# DigitalPSU.net
KiCad netlist of a schematic drawn in EAGLE
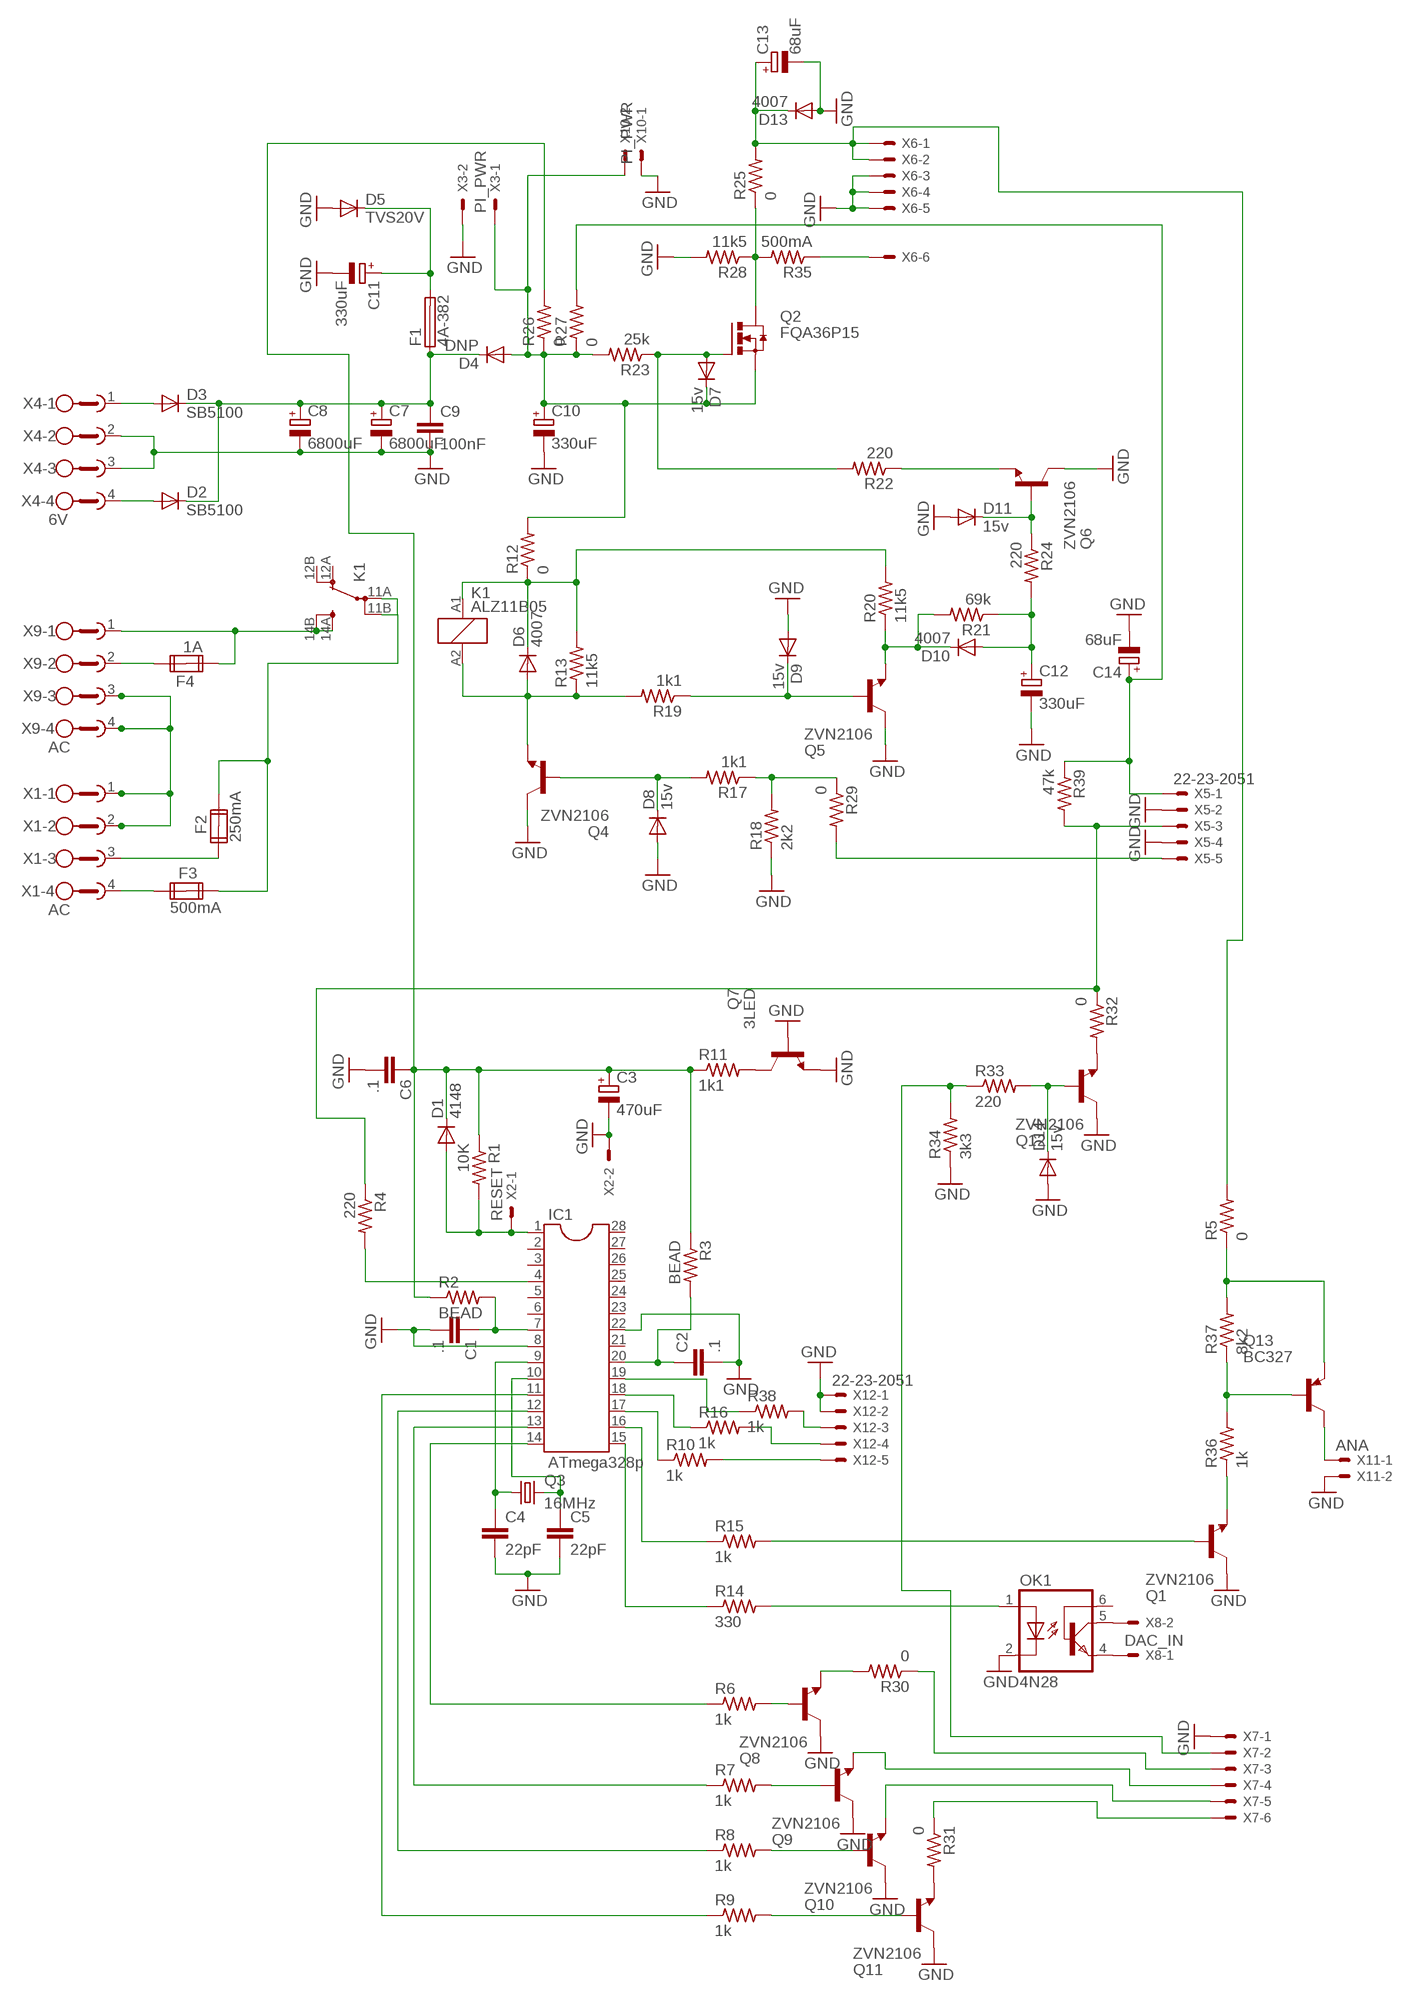
[diagram p0: schematic, sheet 1]

(export (version "E")
  (design (tool "Eeschema 10.0.6"))
  (components
    (comp (ref "C1")
      (value ".1")
      (footprint "eagle-import:C1210K")
      (libsource (lib "eagle-import") (part "C-EUC1210K"))
    )
    (comp (ref "C2")
      (value ".1")
      (footprint "eagle-import:C1210K")
      (libsource (lib "eagle-import") (part "C-EUC1210K"))
    )
    (comp (ref "C3")
      (value "470uF")
      (footprint "eagle-import:E3,5-10")
      (libsource (lib "eagle-import") (part "CPOL-EUE3.5-10"))
    )
    (comp (ref "C4")
      (value "22pF")
      (footprint "eagle-import:C1210K")
      (libsource (lib "eagle-import") (part "C-EUC1210K"))
    )
    (comp (ref "C5")
      (value "22pF")
      (footprint "eagle-import:C1210K")
      (libsource (lib "eagle-import") (part "C-EUC1210K"))
    )
    (comp (ref "C6")
      (value ".1")
      (footprint "eagle-import:C1210K")
      (libsource (lib "eagle-import") (part "C-EUC1210K"))
    )
    (comp (ref "C7")
      (value "6800uF")
      (footprint "eagle-import:EB20D")
      (libsource (lib "eagle-import") (part "CPOL-EUE10-20"))
    )
    (comp (ref "C8")
      (value "6800uF")
      (footprint "eagle-import:EB20D")
      (libsource (lib "eagle-import") (part "CPOL-EUE10-20"))
    )
    (comp (ref "C9")
      (value "100nF")
      (footprint "eagle-import:C10B6")
      (libsource (lib "eagle-import") (part "C10/6"))
    )
    (comp (ref "C10")
      (value "330uF")
      (footprint "eagle-import:E3,5-10")
      (libsource (lib "eagle-import") (part "CPOL-EUE3.5-10"))
    )
    (comp (ref "C11")
      (value "330uF")
      (footprint "eagle-import:E3,5-10")
      (libsource (lib "eagle-import") (part "CPOL-EUE3.5-10"))
    )
    (comp (ref "C12")
      (value "330uF")
      (footprint "eagle-import:E3,5-10")
      (libsource (lib "eagle-import") (part "CPOL-EUE3.5-10"))
    )
    (comp (ref "C13")
      (value "68uF")
      (footprint "eagle-import:E3,5-10")
      (libsource (lib "eagle-import") (part "CPOL-EUE3.5-10"))
    )
    (comp (ref "C14")
      (value "68uF")
      (footprint "eagle-import:E3,5-10")
      (libsource (lib "eagle-import") (part "CPOL-EUE3.5-10"))
    )
    (comp (ref "D1")
      (value "4148")
      (footprint "eagle-import:DO35-7")
      (libsource (lib "eagle-import") (part "1N4148DO35-7"))
    )
    (comp (ref "D2")
      (value "SB5100")
      (footprint "eagle-import:SOD57-10")
      (libsource (lib "eagle-import") (part "BY448"))
    )
    (comp (ref "D3")
      (value "SB5100")
      (footprint "eagle-import:SOD57-10")
      (libsource (lib "eagle-import") (part "BY448"))
    )
    (comp (ref "D4")
      (value "DNP")
      (footprint "eagle-import:DO41-10")
      (libsource (lib "eagle-import") (part "1N4004"))
    )
    (comp (ref "D5")
      (value "TVS20V")
      (footprint "eagle-import:SOD57-10")
      (libsource (lib "eagle-import") (part "BY448"))
    )
    (comp (ref "D6")
      (value "4007")
      (footprint "eagle-import:DO41-10")
      (libsource (lib "eagle-import") (part "1N4004"))
    )
    (comp (ref "D7")
      (value "15v")
      (footprint "eagle-import:DO35-10")
      (libsource (lib "eagle-import") (part "1N4148DO35-10"))
    )
    (comp (ref "D8")
      (value "15v")
      (footprint "eagle-import:DO35-7")
      (libsource (lib "eagle-import") (part "1N4148DO35-7"))
    )
    (comp (ref "D9")
      (value "15v")
      (footprint "eagle-import:DO35-7")
      (libsource (lib "eagle-import") (part "1N4148DO35-7"))
    )
    (comp (ref "D10")
      (value "4007")
      (footprint "eagle-import:DO35-10")
      (libsource (lib "eagle-import") (part "1N4148DO35-10"))
    )
    (comp (ref "D11")
      (value "15v")
      (footprint "eagle-import:DO35-7")
      (libsource (lib "eagle-import") (part "1N4148DO35-7"))
    )
    (comp (ref "D13")
      (value "4007")
      (footprint "eagle-import:DO41-10")
      (libsource (lib "eagle-import") (part "1N4004"))
    )
    (comp (ref "D14")
      (value "15v")
      (footprint "eagle-import:DO35-7")
      (libsource (lib "eagle-import") (part "1N4148DO35-7"))
    )
    (comp (ref "F1")
      (value "4A-382")
      (footprint "eagle-import:19560")
      (fields (field (name "MPN") "56000001009"))
      (libsource (lib "eagle-import") (part "19560"))
    )
    (comp (ref "F2")
      (value "250mA")
      (footprint "eagle-import:FUSE1")
      (libsource (lib "eagle-import") (part "FUSE2P"))
    )
    (comp (ref "F3")
      (value "500mA")
      (footprint "eagle-import:FUSE1")
      (libsource (lib "eagle-import") (part "FUSE2P"))
    )
    (comp (ref "F4")
      (value "1A")
      (footprint "eagle-import:FUSE1")
      (libsource (lib "eagle-import") (part "FUSE2P"))
    )
    (comp (ref "IC1")
      (value "ATmega328p")
      (footprint "eagle-import:DIL28-3")
      (libsource (lib "eagle-import") (part "DIL28-3"))
    )
    (comp (ref "K1")
      (value "ALZ11B05")
      (footprint "eagle-import:RT-C_O16A5")
      (fields (field (name "MPN") "RT314730"))
      (libsource (lib "eagle-import") (part "RT314730"))
    )
    (comp (ref "OK1")
      (value "4N28")
      (footprint "eagle-import:DIL06")
      (fields (field (name "MF") "FAIRCHILD SEMICONDUCTOR") (field (name "MPN") "4N35"))
      (libsource (lib "eagle-import") (part "4N35"))
    )
    (comp (ref "Q1")
      (value "ZVN2106")
      (footprint "eagle-import:TO92-EBC")
      (libsource (lib "eagle-import") (part "BC550B"))
    )
    (comp (ref "Q2")
      (value "FQA36P15")
      (footprint "eagle-import:TO247BV")
      (libsource (lib "eagle-import") (part "IRFP240"))
    )
    (comp (ref "Q3")
      (value "16MHz")
      (footprint "eagle-import:HC49_S")
      (libsource (lib "eagle-import") (part "CRYSTALHC49S"))
    )
    (comp (ref "Q4")
      (value "ZVN2106")
      (footprint "eagle-import:TO92-EBC")
      (libsource (lib "eagle-import") (part "BC550B"))
    )
    (comp (ref "Q5")
      (value "ZVN2106")
      (footprint "eagle-import:TO92-EBC")
      (libsource (lib "eagle-import") (part "BC550B"))
    )
    (comp (ref "Q6")
      (value "ZVN2106")
      (footprint "eagle-import:TO92-EBC")
      (libsource (lib "eagle-import") (part "BC550B"))
    )
    (comp (ref "Q7")
      (value "3LED")
      (footprint "eagle-import:TO92-EBC")
      (libsource (lib "eagle-import") (part "BC546A"))
    )
    (comp (ref "Q8")
      (value "ZVN2106")
      (footprint "eagle-import:TO92-EBC")
      (libsource (lib "eagle-import") (part "BC550B"))
    )
    (comp (ref "Q9")
      (value "ZVN2106")
      (footprint "eagle-import:TO92-EBC")
      (libsource (lib "eagle-import") (part "BC550B"))
    )
    (comp (ref "Q10")
      (value "ZVN2106")
      (footprint "eagle-import:TO92-EBC")
      (libsource (lib "eagle-import") (part "BC550B"))
    )
    (comp (ref "Q11")
      (value "ZVN2106")
      (footprint "eagle-import:TO92-EBC")
      (libsource (lib "eagle-import") (part "BC550B"))
    )
    (comp (ref "Q12")
      (value "ZVN2106")
      (footprint "eagle-import:TO92-EBC")
      (libsource (lib "eagle-import") (part "BC550B"))
    )
    (comp (ref "Q13")
      (value "BC327")
      (footprint "eagle-import:TO92-EBC")
      (libsource (lib "eagle-import") (part "BC327-25"))
    )
    (comp (ref "R1")
      (value "10K")
      (footprint "eagle-import:0309_10")
      (libsource (lib "eagle-import") (part "R-US_0309/10"))
    )
    (comp (ref "R2")
      (value "BEAD")
      (footprint "eagle-import:0309_10")
      (libsource (lib "eagle-import") (part "R-US_0309/10"))
    )
    (comp (ref "R3")
      (value "BEAD")
      (footprint "eagle-import:0309_12")
      (libsource (lib "eagle-import") (part "R-US_0309/12"))
    )
    (comp (ref "R4")
      (value "220")
      (footprint "eagle-import:0309_12")
      (libsource (lib "eagle-import") (part "R-US_0309/12"))
    )
    (comp (ref "R5")
      (value "0")
      (footprint "eagle-import:0309_12")
      (libsource (lib "eagle-import") (part "R-US_0309/12"))
    )
    (comp (ref "R6")
      (value "1k")
      (footprint "eagle-import:R1210")
      (libsource (lib "eagle-import") (part "R-US_R1210"))
    )
    (comp (ref "R7")
      (value "1k")
      (footprint "eagle-import:R1210")
      (libsource (lib "eagle-import") (part "R-US_R1210"))
    )
    (comp (ref "R8")
      (value "1k")
      (footprint "eagle-import:R1210")
      (libsource (lib "eagle-import") (part "R-US_R1210"))
    )
    (comp (ref "R9")
      (value "1k")
      (footprint "eagle-import:R1210")
      (libsource (lib "eagle-import") (part "R-US_R1210"))
    )
    (comp (ref "R10")
      (value "1k")
      (footprint "eagle-import:R1210")
      (libsource (lib "eagle-import") (part "R-US_R1210"))
    )
    (comp (ref "R11")
      (value "1k1")
      (footprint "eagle-import:0309_10")
      (libsource (lib "eagle-import") (part "R-US_0309/10"))
    )
    (comp (ref "R12")
      (value "0")
      (footprint "eagle-import:0309_10")
      (libsource (lib "eagle-import") (part "R-US_0309/10"))
    )
    (comp (ref "R13")
      (value "11k5")
      (footprint "eagle-import:0309_10")
      (libsource (lib "eagle-import") (part "R-US_0309/10"))
    )
    (comp (ref "R14")
      (value "330")
      (footprint "eagle-import:0309_10")
      (libsource (lib "eagle-import") (part "R-US_0309/10"))
    )
    (comp (ref "R15")
      (value "1k")
      (footprint "eagle-import:R1210")
      (libsource (lib "eagle-import") (part "R-US_R1210"))
    )
    (comp (ref "R16")
      (value "1k")
      (footprint "eagle-import:R1210")
      (libsource (lib "eagle-import") (part "R-US_R1210"))
    )
    (comp (ref "R17")
      (value "1k1")
      (footprint "eagle-import:0309_10")
      (libsource (lib "eagle-import") (part "R-US_0309/10"))
    )
    (comp (ref "R18")
      (value "2k2")
      (footprint "eagle-import:0309_10")
      (libsource (lib "eagle-import") (part "R-US_0309/10"))
    )
    (comp (ref "R19")
      (value "1k1")
      (footprint "eagle-import:0309_10")
      (libsource (lib "eagle-import") (part "R-US_0309/10"))
    )
    (comp (ref "R20")
      (value "11k5")
      (footprint "eagle-import:0309_10")
      (libsource (lib "eagle-import") (part "R-US_0309/10"))
    )
    (comp (ref "R21")
      (value "69k")
      (footprint "eagle-import:0309_10")
      (libsource (lib "eagle-import") (part "R-US_0309/10"))
    )
    (comp (ref "R22")
      (value "220")
      (footprint "eagle-import:0309_10")
      (libsource (lib "eagle-import") (part "R-US_0309/10"))
    )
    (comp (ref "R23")
      (value "25k")
      (footprint "eagle-import:0309_10")
      (libsource (lib "eagle-import") (part "R-US_0309/10"))
    )
    (comp (ref "R24")
      (value "220")
      (footprint "eagle-import:0309_10")
      (libsource (lib "eagle-import") (part "R-US_0309/10"))
    )
    (comp (ref "R25")
      (value "0")
      (footprint "eagle-import:0309_12")
      (libsource (lib "eagle-import") (part "R-US_0309/12"))
    )
    (comp (ref "R26")
      (value "0")
      (footprint "eagle-import:0309_12")
      (libsource (lib "eagle-import") (part "R-US_0309/12"))
    )
    (comp (ref "R27")
      (value "0")
      (footprint "eagle-import:0309_12")
      (libsource (lib "eagle-import") (part "R-US_0309/12"))
    )
    (comp (ref "R28")
      (value "11k5")
      (footprint "eagle-import:0204_5")
      (libsource (lib "eagle-import") (part "R-US_0204/5"))
    )
    (comp (ref "R29")
      (value "0")
      (footprint "eagle-import:0309_10")
      (libsource (lib "eagle-import") (part "R-US_0309/10"))
    )
    (comp (ref "R30")
      (value "0")
      (footprint "eagle-import:0309_10")
      (libsource (lib "eagle-import") (part "R-US_0309/10"))
    )
    (comp (ref "R31")
      (value "0")
      (footprint "eagle-import:0309_12")
      (libsource (lib "eagle-import") (part "R-US_0309/12"))
    )
    (comp (ref "R32")
      (value "0")
      (footprint "eagle-import:0309_12")
      (libsource (lib "eagle-import") (part "R-US_0309/12"))
    )
    (comp (ref "R33")
      (value "220")
      (footprint "eagle-import:0309_12")
      (libsource (lib "eagle-import") (part "R-US_0309/12"))
    )
    (comp (ref "R34")
      (value "3k3")
      (footprint "eagle-import:0309_12")
      (libsource (lib "eagle-import") (part "R-US_0309/12"))
    )
    (comp (ref "R35")
      (value "500mA")
      (footprint "eagle-import:0204_5")
      (libsource (lib "eagle-import") (part "R-US_0204/5"))
    )
    (comp (ref "R36")
      (value "1k")
      (footprint "eagle-import:R1210")
      (libsource (lib "eagle-import") (part "R-US_R1210"))
    )
    (comp (ref "R37")
      (value "8k2")
      (footprint "eagle-import:R1210")
      (libsource (lib "eagle-import") (part "R-US_R1210"))
    )
    (comp (ref "R38")
      (value "1k")
      (footprint "eagle-import:R1210")
      (libsource (lib "eagle-import") (part "R-US_R1210"))
    )
    (comp (ref "R39")
      (value "47k")
      (footprint "eagle-import:0309_10")
      (libsource (lib "eagle-import") (part "R-US_0309/10"))
    )
    (comp (ref "X1")
      (value "AC")
      (footprint "eagle-import:GMSTBA4")
      (fields (field (name "MF") "FARNELL") (field (name "MPN") "1757268"))
      (libsource (lib "eagle-import") (part "GMSTBA4"))
    )
    (comp (ref "X2")
      (value "RESET")
      (footprint "eagle-import:22-23-2021")
      (fields (field (name "MF") "MOLEX") (field (name "MPN") "22-23-2021"))
      (libsource (lib "eagle-import") (part "22-23-2021"))
    )
    (comp (ref "X3")
      (value "PI_PWR")
      (footprint "eagle-import:22-23-2021")
      (fields (field (name "MF") "MOLEX") (field (name "MPN") "22-23-2021"))
      (libsource (lib "eagle-import") (part "22-23-2021"))
    )
    (comp (ref "X4")
      (value "6V")
      (footprint "eagle-import:GMSTBA4")
      (fields (field (name "MF") "FARNELL") (field (name "MPN") "1757268"))
      (libsource (lib "eagle-import") (part "GMSTBA4"))
    )
    (comp (ref "X5")
      (value "22-23-2051")
      (footprint "eagle-import:22-23-2051")
      (fields (field (name "MF") "MOLEX"))
      (libsource (lib "eagle-import") (part "22-23-2051"))
    )
    (comp (ref "X6")
      (value "22-23-2061")
      (footprint "eagle-import:22-23-2061")
      (fields (field (name "MF") "MOLEX"))
      (libsource (lib "eagle-import") (part "22-23-2061"))
    )
    (comp (ref "X7")
      (value "22-23-2061")
      (footprint "eagle-import:22-23-2061")
      (fields (field (name "MF") "MOLEX"))
      (libsource (lib "eagle-import") (part "22-23-2061"))
    )
    (comp (ref "X8")
      (value "DAC_IN")
      (footprint "eagle-import:22-23-2021")
      (fields (field (name "MF") "MOLEX") (field (name "MPN") "22-23-2021"))
      (libsource (lib "eagle-import") (part "22-23-2021"))
    )
    (comp (ref "X9")
      (value "AC")
      (footprint "eagle-import:GMSTBA4")
      (fields (field (name "MF") "FARNELL") (field (name "MPN") "1757268"))
      (libsource (lib "eagle-import") (part "GMSTBA4"))
    )
    (comp (ref "X10")
      (value "PI_PWR")
      (footprint "eagle-import:22-23-2021")
      (fields (field (name "MF") "MOLEX") (field (name "MPN") "22-23-2021"))
      (libsource (lib "eagle-import") (part "22-23-2021"))
    )
    (comp (ref "X11")
      (value "ANA")
      (footprint "eagle-import:22-23-2021")
      (fields (field (name "MF") "MOLEX") (field (name "MPN") "22-23-2021"))
      (libsource (lib "eagle-import") (part "22-23-2021"))
    )
    (comp (ref "X12")
      (value "22-23-2051")
      (footprint "eagle-import:22-23-2051")
      (fields (field (name "MF") "MOLEX"))
      (libsource (lib "eagle-import") (part "22-23-2051"))
    )
  )
  (nets
    (net (code "1") (name "GND") (class "Default")
      (node (ref "C1") (pin "2") (pinfunction "2_2") (pintype "passive"))
      (node (ref "C10") (pin "-") (pinfunction "-_-") (pintype "passive"))
      (node (ref "C11") (pin "-") (pinfunction "-_-") (pintype "passive"))
      (node (ref "C12") (pin "-") (pinfunction "-_-") (pintype "passive"))
      (node (ref "C13") (pin "-") (pinfunction "-_-") (pintype "passive"))
      (node (ref "C14") (pin "-") (pinfunction "-_-") (pintype "passive"))
      (node (ref "C2") (pin "2") (pinfunction "2_2") (pintype "passive"))
      (node (ref "C3") (pin "-") (pinfunction "-_-") (pintype "passive"))
      (node (ref "C4") (pin "2") (pinfunction "2_2") (pintype "passive"))
      (node (ref "C5") (pin "2") (pinfunction "2_2") (pintype "passive"))
      (node (ref "C6") (pin "2") (pinfunction "2_2") (pintype "passive"))
      (node (ref "C7") (pin "-") (pinfunction "-_-") (pintype "passive"))
      (node (ref "C8") (pin "-") (pinfunction "-_-") (pintype "passive"))
      (node (ref "C9") (pin "2") (pinfunction "2_2") (pintype "passive"))
      (node (ref "D11") (pin "A") (pinfunction "A_A") (pintype "passive"))
      (node (ref "D13") (pin "A") (pinfunction "A_A") (pintype "passive"))
      (node (ref "D14") (pin "A") (pinfunction "A_A") (pintype "passive"))
      (node (ref "D5") (pin "A") (pinfunction "A_A") (pintype "passive"))
      (node (ref "D8") (pin "A") (pinfunction "A_A") (pintype "passive"))
      (node (ref "D9") (pin "A") (pinfunction "A_A") (pintype "passive"))
      (node (ref "IC1") (pin "22") (pinfunction "22_22") (pintype "passive"))
      (node (ref "IC1") (pin "8") (pinfunction "8_8") (pintype "passive"))
      (node (ref "OK1") (pin "2") (pinfunction "C_2") (pintype "passive"))
      (node (ref "Q1") (pin "C") (pinfunction "C_C") (pintype "passive"))
      (node (ref "Q10") (pin "C") (pinfunction "C_C") (pintype "passive"))
      (node (ref "Q11") (pin "C") (pinfunction "C_C") (pintype "passive"))
      (node (ref "Q12") (pin "C") (pinfunction "C_C") (pintype "passive"))
      (node (ref "Q4") (pin "C") (pinfunction "C_C") (pintype "passive"))
      (node (ref "Q5") (pin "C") (pinfunction "C_C") (pintype "passive"))
      (node (ref "Q6") (pin "C") (pinfunction "C_C") (pintype "passive"))
      (node (ref "Q7") (pin "B") (pinfunction "B_B") (pintype "passive"))
      (node (ref "Q7") (pin "E") (pinfunction "E_E") (pintype "passive"))
      (node (ref "Q8") (pin "C") (pinfunction "C_C") (pintype "passive"))
      (node (ref "Q9") (pin "C") (pinfunction "C_C") (pintype "passive"))
      (node (ref "R18") (pin "1") (pinfunction "1_1") (pintype "passive"))
      (node (ref "R28") (pin "2") (pinfunction "2_2") (pintype "passive"))
      (node (ref "R34") (pin "1") (pinfunction "1_1") (pintype "passive"))
      (node (ref "X10") (pin "1") (pinfunction "S_1") (pintype "passive"))
      (node (ref "X11") (pin "2") (pinfunction "S_2") (pintype "passive"))
      (node (ref "X12") (pin "1") (pinfunction "S_1") (pintype "passive"))
      (node (ref "X12") (pin "2") (pinfunction "S_2") (pintype "passive"))
      (node (ref "X2") (pin "2") (pinfunction "S_2") (pintype "passive"))
      (node (ref "X3") (pin "2") (pinfunction "S_2") (pintype "passive"))
      (node (ref "X4") (pin "2") (pinfunction "1_2") (pintype "passive"))
      (node (ref "X4") (pin "3") (pinfunction "1_3") (pintype "passive"))
      (node (ref "X5") (pin "2") (pinfunction "S_2") (pintype "passive"))
      (node (ref "X5") (pin "4") (pinfunction "S_4") (pintype "passive"))
      (node (ref "X6") (pin "3") (pinfunction "S_3") (pintype "passive"))
      (node (ref "X6") (pin "4") (pinfunction "S_4") (pintype "passive"))
      (node (ref "X6") (pin "5") (pinfunction "S_5") (pintype "passive"))
      (node (ref "X7") (pin "1") (pinfunction "S_1") (pintype "passive"))
    )
    (net (code "2") (name "Net-(C1-Pad1)") (class "Default")
      (node (ref "C1") (pin "1") (pinfunction "1_1") (pintype "passive"))
      (node (ref "IC1") (pin "7") (pinfunction "7_7") (pintype "passive"))
      (node (ref "R2") (pin "2") (pinfunction "2_2") (pintype "passive"))
    )
    (net (code "3") (name "Net-(C2-Pad1)") (class "Default")
      (node (ref "C2") (pin "1") (pinfunction "1_1") (pintype "passive"))
      (node (ref "IC1") (pin "20") (pinfunction "20_20") (pintype "passive"))
      (node (ref "R3") (pin "2") (pinfunction "2_2") (pintype "passive"))
    )
    (net (code "4") (name "Net-(C3-Pad+)") (class "Default")
      (node (ref "C3") (pin "+") (pinfunction "+_+") (pintype "passive"))
      (node (ref "C6") (pin "1") (pinfunction "1_1") (pintype "passive"))
      (node (ref "D1") (pin "C") (pinfunction "C_C") (pintype "passive"))
      (node (ref "R1") (pin "1") (pinfunction "1_1") (pintype "passive"))
      (node (ref "R11") (pin "1") (pinfunction "1_1") (pintype "passive"))
      (node (ref "R2") (pin "1") (pinfunction "1_1") (pintype "passive"))
      (node (ref "R26") (pin "2") (pinfunction "2_2") (pintype "passive"))
      (node (ref "R3") (pin "1") (pinfunction "1_1") (pintype "passive"))
    )
    (net (code "5") (name "Net-(C4-Pad1)") (class "Default")
      (node (ref "C4") (pin "1") (pinfunction "1_1") (pintype "passive"))
      (node (ref "IC1") (pin "9") (pinfunction "9_9") (pintype "passive"))
      (node (ref "Q3") (pin "1") (pinfunction "1_1") (pintype "passive"))
    )
    (net (code "6") (name "Net-(C5-Pad1)") (class "Default")
      (node (ref "C5") (pin "1") (pinfunction "1_1") (pintype "passive"))
      (node (ref "IC1") (pin "10") (pinfunction "10_10") (pintype "passive"))
      (node (ref "Q3") (pin "2") (pinfunction "2_2") (pintype "passive"))
    )
    (net (code "7") (name "Net-(C7-Pad+)") (class "Default")
      (node (ref "C7") (pin "+") (pinfunction "+_+") (pintype "passive"))
      (node (ref "C8") (pin "+") (pinfunction "+_+") (pintype "passive"))
      (node (ref "C9") (pin "1") (pinfunction "1_1") (pintype "passive"))
      (node (ref "D2") (pin "C") (pinfunction "C_C") (pintype "passive"))
      (node (ref "D3") (pin "C") (pinfunction "C_C") (pintype "passive"))
      (node (ref "D4") (pin "C") (pinfunction "C_C") (pintype "passive"))
      (node (ref "F1") (pin "1") (pinfunction "1_1") (pintype "passive"))
    )
    (net (code "8") (name "Net-(C11-Pad+)") (class "Default")
      (node (ref "C11") (pin "+") (pinfunction "+_+") (pintype "passive"))
      (node (ref "D5") (pin "C") (pinfunction "C_C") (pintype "passive"))
      (node (ref "F1") (pin "2") (pinfunction "2_2") (pintype "passive"))
    )
    (net (code "9") (name "Net-(C12-Pad+)") (class "Default")
      (node (ref "C12") (pin "+") (pinfunction "+_+") (pintype "passive"))
      (node (ref "D10") (pin "A") (pinfunction "A_A") (pintype "passive"))
      (node (ref "R21") (pin "1") (pinfunction "1_1") (pintype "passive"))
      (node (ref "R24") (pin "2") (pinfunction "2_2") (pintype "passive"))
    )
    (net (code "10") (name "Net-(D3-PadA)") (class "Default")
      (node (ref "D3") (pin "A") (pinfunction "A_A") (pintype "passive"))
      (node (ref "X4") (pin "1") (pinfunction "1_1") (pintype "passive"))
    )
    (net (code "11") (name "Net-(D7-PadA)") (class "Default")
      (node (ref "D7") (pin "A") (pinfunction "A_A") (pintype "passive"))
      (node (ref "Q2") (pin "G") (pinfunction "G_G") (pintype "passive"))
      (node (ref "R22") (pin "2") (pinfunction "2_2") (pintype "passive"))
      (node (ref "R23") (pin "1") (pinfunction "1_1") (pintype "passive"))
    )
    (net (code "12") (name "Net-(D8-PadC)") (class "Default")
      (node (ref "D8") (pin "C") (pinfunction "C_C") (pintype "passive"))
      (node (ref "Q4") (pin "B") (pinfunction "B_B") (pintype "passive"))
      (node (ref "R17") (pin "2") (pinfunction "2_2") (pintype "passive"))
    )
    (net (code "13") (name "Net-(D9-PadC)") (class "Default")
      (node (ref "D9") (pin "C") (pinfunction "C_C") (pintype "passive"))
      (node (ref "Q5") (pin "B") (pinfunction "B_B") (pintype "passive"))
      (node (ref "R19") (pin "1") (pinfunction "1_1") (pintype "passive"))
    )
    (net (code "14") (name "Net-(D10-PadC)") (class "Default")
      (node (ref "D10") (pin "C") (pinfunction "C_C") (pintype "passive"))
      (node (ref "Q5") (pin "E") (pinfunction "E_E") (pintype "passive"))
      (node (ref "R20") (pin "1") (pinfunction "1_1") (pintype "passive"))
      (node (ref "R21") (pin "2") (pinfunction "2_2") (pintype "passive"))
    )
    (net (code "15") (name "Net-(D11-PadC)") (class "Default")
      (node (ref "D11") (pin "C") (pinfunction "C_C") (pintype "passive"))
      (node (ref "Q6") (pin "B") (pinfunction "B_B") (pintype "passive"))
      (node (ref "R24") (pin "1") (pinfunction "1_1") (pintype "passive"))
    )
    (net (code "16") (name "Net-(D14-PadC)") (class "Default")
      (node (ref "D14") (pin "C") (pinfunction "C_C") (pintype "passive"))
      (node (ref "Q12") (pin "B") (pinfunction "B_B") (pintype "passive"))
      (node (ref "R33") (pin "2") (pinfunction "2_2") (pintype "passive"))
    )
    (net (code "17") (name "Net-(IC1-Pad4)") (class "Default")
      (node (ref "IC1") (pin "4") (pinfunction "4_4") (pintype "passive"))
      (node (ref "R4") (pin "2") (pinfunction "2_2") (pintype "passive"))
    )
    (net (code "18") (name "Net-(IC1-Pad11)") (class "Default")
      (node (ref "IC1") (pin "11") (pinfunction "11_11") (pintype "passive"))
      (node (ref "R9") (pin "1") (pinfunction "1_1") (pintype "passive"))
    )
    (net (code "19") (name "Net-(IC1-Pad12)") (class "Default")
      (node (ref "IC1") (pin "12") (pinfunction "12_12") (pintype "passive"))
      (node (ref "R8") (pin "1") (pinfunction "1_1") (pintype "passive"))
    )
    (net (code "20") (name "Net-(IC1-Pad13)") (class "Default")
      (node (ref "IC1") (pin "13") (pinfunction "13_13") (pintype "passive"))
      (node (ref "R7") (pin "1") (pinfunction "1_1") (pintype "passive"))
    )
    (net (code "21") (name "Net-(IC1-Pad14)") (class "Default")
      (node (ref "IC1") (pin "14") (pinfunction "14_14") (pintype "passive"))
      (node (ref "R6") (pin "1") (pinfunction "1_1") (pintype "passive"))
    )
    (net (code "22") (name "Net-(IC1-Pad15)") (class "Default")
      (node (ref "IC1") (pin "15") (pinfunction "15_15") (pintype "passive"))
      (node (ref "R14") (pin "1") (pinfunction "1_1") (pintype "passive"))
    )
    (net (code "23") (name "Net-(IC1-Pad16)") (class "Default")
      (node (ref "IC1") (pin "16") (pinfunction "16_16") (pintype "passive"))
      (node (ref "R15") (pin "1") (pinfunction "1_1") (pintype "passive"))
    )
    (net (code "24") (name "Net-(IC1-Pad17)") (class "Default")
      (node (ref "IC1") (pin "17") (pinfunction "17_17") (pintype "passive"))
      (node (ref "R10") (pin "1") (pinfunction "1_1") (pintype "passive"))
    )
    (net (code "25") (name "Net-(IC1-Pad18)") (class "Default")
      (node (ref "IC1") (pin "18") (pinfunction "18_18") (pintype "passive"))
      (node (ref "R16") (pin "1") (pinfunction "1_1") (pintype "passive"))
    )
    (net (code "26") (name "Net-(IC1-Pad19)") (class "Default")
      (node (ref "IC1") (pin "19") (pinfunction "19_19") (pintype "passive"))
      (node (ref "R38") (pin "1") (pinfunction "1_1") (pintype "passive"))
    )
    (net (code "27") (name "Net-(K1A-1)") (class "Default")
      (node (ref "D6") (pin "C") (pinfunction "C_C") (pintype "passive"))
      (node (ref "K1") (pin "A1") (pinfunction "1_A1") (pintype "passive"))
      (node (ref "R12") (pin "1") (pinfunction "1_1") (pintype "passive"))
      (node (ref "R13") (pin "2") (pinfunction "2_2") (pintype "passive"))
      (node (ref "R20") (pin "2") (pinfunction "2_2") (pintype "passive"))
    )
    (net (code "28") (name "Net-(K1A-2)") (class "Default")
      (node (ref "D6") (pin "A") (pinfunction "A_A") (pintype "passive"))
      (node (ref "K1") (pin "A2") (pinfunction "2_A2") (pintype "passive"))
      (node (ref "Q4") (pin "E") (pinfunction "E_E") (pintype "passive"))
      (node (ref "R13") (pin "1") (pinfunction "1_1") (pintype "passive"))
      (node (ref "R19") (pin "2") (pinfunction "2_2") (pintype "passive"))
    )
    (net (code "29") (name "Net-(K1B-PA)") (class "Default")
      (node (ref "F2") (pin "2A") (pinfunction "2A_2A") (pintype "passive"))
      (node (ref "F3") (pin "2A") (pinfunction "2A_2A") (pintype "passive"))
      (node (ref "K1") (pin "11A") (pinfunction "PA_11A") (pintype "passive"))
      (node (ref "K1") (pin "11B") (pinfunction "PB_11B") (pintype "passive"))
    )
    (net (code "30") (name "Net-(K1B-SA)") (class "Default")
      (node (ref "F4") (pin "1A") (pinfunction "1A_1A") (pintype "passive"))
      (node (ref "K1") (pin "14A") (pinfunction "SA_14A") (pintype "passive"))
      (node (ref "K1") (pin "14B") (pinfunction "SB_14B") (pintype "passive"))
      (node (ref "X9") (pin "1") (pinfunction "1_1") (pintype "passive"))
    )
    (net (code "31") (name "Net-(OK1-A)") (class "Default")
      (node (ref "OK1") (pin "1") (pinfunction "A_1") (pintype "passive"))
      (node (ref "R14") (pin "2") (pinfunction "2_2") (pintype "passive"))
    )
    (net (code "32") (name "Net-(OK1-COL)") (class "Default")
      (node (ref "OK1") (pin "5") (pinfunction "COL_5") (pintype "passive"))
      (node (ref "X8") (pin "2") (pinfunction "S_2") (pintype "passive"))
    )
    (net (code "33") (name "Net-(OK1-EMI)") (class "Default")
      (node (ref "OK1") (pin "4") (pinfunction "EMI_4") (pintype "passive"))
      (node (ref "X8") (pin "1") (pinfunction "S_1") (pintype "passive"))
    )
    (net (code "34") (name "Net-(Q1-PadB)") (class "Default")
      (node (ref "Q1") (pin "B") (pinfunction "B_B") (pintype "passive"))
      (node (ref "R15") (pin "2") (pinfunction "2_2") (pintype "passive"))
    )
    (net (code "35") (name "Net-(Q1-PadE)") (class "Default")
      (node (ref "Q1") (pin "E") (pinfunction "E_E") (pintype "passive"))
      (node (ref "R36") (pin "1") (pinfunction "1_1") (pintype "passive"))
    )
    (net (code "36") (name "Net-(Q2-PadD)") (class "Default")
      (node (ref "Q2") (pin "D") (pinfunction "D_D") (pintype "passive"))
      (node (ref "R25") (pin "1") (pinfunction "1_1") (pintype "passive"))
      (node (ref "R28") (pin "1") (pinfunction "1_1") (pintype "passive"))
      (node (ref "R35") (pin "2") (pinfunction "2_2") (pintype "passive"))
    )
    (net (code "37") (name "Net-(Q6-PadE)") (class "Default")
      (node (ref "Q6") (pin "E") (pinfunction "E_E") (pintype "passive"))
      (node (ref "R22") (pin "1") (pinfunction "1_1") (pintype "passive"))
    )
    (net (code "38") (name "Net-(Q7-PadC)") (class "Default")
      (node (ref "Q7") (pin "C") (pinfunction "C_C") (pintype "passive"))
      (node (ref "R11") (pin "2") (pinfunction "2_2") (pintype "passive"))
    )
    (net (code "39") (name "Net-(Q8-PadB)") (class "Default")
      (node (ref "Q8") (pin "B") (pinfunction "B_B") (pintype "passive"))
      (node (ref "R6") (pin "2") (pinfunction "2_2") (pintype "passive"))
    )
    (net (code "40") (name "Net-(Q8-PadE)") (class "Default")
      (node (ref "Q8") (pin "E") (pinfunction "E_E") (pintype "passive"))
      (node (ref "R30") (pin "2") (pinfunction "2_2") (pintype "passive"))
    )
    (net (code "41") (name "Net-(Q9-PadB)") (class "Default")
      (node (ref "Q9") (pin "B") (pinfunction "B_B") (pintype "passive"))
      (node (ref "R7") (pin "2") (pinfunction "2_2") (pintype "passive"))
    )
    (net (code "42") (name "Net-(Q10-PadB)") (class "Default")
      (node (ref "Q10") (pin "B") (pinfunction "B_B") (pintype "passive"))
      (node (ref "R8") (pin "2") (pinfunction "2_2") (pintype "passive"))
    )
    (net (code "43") (name "Net-(Q11-PadB)") (class "Default")
      (node (ref "Q11") (pin "B") (pinfunction "B_B") (pintype "passive"))
      (node (ref "R9") (pin "2") (pinfunction "2_2") (pintype "passive"))
    )
    (net (code "44") (name "Net-(Q11-PadE)") (class "Default")
      (node (ref "Q11") (pin "E") (pinfunction "E_E") (pintype "passive"))
      (node (ref "R31") (pin "2") (pinfunction "2_2") (pintype "passive"))
    )
    (net (code "45") (name "Net-(Q12-PadE)") (class "Default")
      (node (ref "Q12") (pin "E") (pinfunction "E_E") (pintype "passive"))
      (node (ref "R32") (pin "2") (pinfunction "2_2") (pintype "passive"))
    )
    (net (code "46") (name "Net-(Q13-PadB)") (class "Default")
      (node (ref "Q13") (pin "B") (pinfunction "B_B") (pintype "passive"))
      (node (ref "R36") (pin "2") (pinfunction "2_2") (pintype "passive"))
      (node (ref "R37") (pin "1") (pinfunction "1_1") (pintype "passive"))
    )
    (net (code "47") (name "Net-(Q13-PadE)") (class "Default")
      (node (ref "Q13") (pin "E") (pinfunction "E_E") (pintype "passive"))
      (node (ref "R37") (pin "2") (pinfunction "2_2") (pintype "passive"))
      (node (ref "R5") (pin "1") (pinfunction "1_1") (pintype "passive"))
    )
    (net (code "48") (name "Net-(R17-Pad1)") (class "Default")
      (node (ref "R17") (pin "1") (pinfunction "1_1") (pintype "passive"))
      (node (ref "R18") (pin "2") (pinfunction "2_2") (pintype "passive"))
      (node (ref "R29") (pin "1") (pinfunction "1_1") (pintype "passive"))
    )
    (net (code "49") (name "Net-(X1B-1)") (class "Default")
      (node (ref "X1") (pin "1") (pinfunction "1_1") (pintype "passive"))
      (node (ref "X1") (pin "2") (pinfunction "1_2") (pintype "passive"))
      (node (ref "X9") (pin "3") (pinfunction "1_3") (pintype "passive"))
      (node (ref "X9") (pin "4") (pinfunction "1_4") (pintype "passive"))
    )
    (net (code "50") (name "Net-(X1C-1)") (class "Default")
      (node (ref "F2") (pin "1A") (pinfunction "1A_1A") (pintype "passive"))
      (node (ref "X1") (pin "3") (pinfunction "1_3") (pintype "passive"))
    )
    (net (code "51") (name "Net-(X1D-1)") (class "Default")
      (node (ref "F3") (pin "1A") (pinfunction "1A_1A") (pintype "passive"))
      (node (ref "X1") (pin "4") (pinfunction "1_4") (pintype "passive"))
    )
    (net (code "52") (name "Net-(X2A-S)") (class "Default")
      (node (ref "D1") (pin "A") (pinfunction "A_A") (pintype "passive"))
      (node (ref "IC1") (pin "1") (pinfunction "1_1") (pintype "passive"))
      (node (ref "R1") (pin "2") (pinfunction "2_2") (pintype "passive"))
      (node (ref "X2") (pin "1") (pinfunction "S_1") (pintype "passive"))
    )
    (net (code "53") (name "Net-(X4D-1)") (class "Default")
      (node (ref "D2") (pin "A") (pinfunction "A_A") (pintype "passive"))
      (node (ref "X4") (pin "4") (pinfunction "1_4") (pintype "passive"))
    )
    (net (code "54") (name "Net-(X5A-S)") (class "Default")
      (node (ref "C14") (pin "+") (pinfunction "+_+") (pintype "passive"))
      (node (ref "R27") (pin "2") (pinfunction "2_2") (pintype "passive"))
      (node (ref "R39") (pin "1") (pinfunction "1_1") (pintype "passive"))
      (node (ref "X5") (pin "1") (pinfunction "S_1") (pintype "passive"))
    )
    (net (code "55") (name "Net-(X5C-S)") (class "Default")
      (node (ref "R32") (pin "1") (pinfunction "1_1") (pintype "passive"))
      (node (ref "R39") (pin "2") (pinfunction "2_2") (pintype "passive"))
      (node (ref "R4") (pin "1") (pinfunction "1_1") (pintype "passive"))
      (node (ref "X5") (pin "3") (pinfunction "S_3") (pintype "passive"))
    )
    (net (code "56") (name "Net-(X5E-S)") (class "Default")
      (node (ref "R29") (pin "2") (pinfunction "2_2") (pintype "passive"))
      (node (ref "X5") (pin "5") (pinfunction "S_5") (pintype "passive"))
    )
    (net (code "57") (name "Net-(X6A-S)") (class "Default")
      (node (ref "C13") (pin "+") (pinfunction "+_+") (pintype "passive"))
      (node (ref "D13") (pin "C") (pinfunction "C_C") (pintype "passive"))
      (node (ref "R25") (pin "2") (pinfunction "2_2") (pintype "passive"))
      (node (ref "R5") (pin "2") (pinfunction "2_2") (pintype "passive"))
      (node (ref "X6") (pin "1") (pinfunction "S_1") (pintype "passive"))
      (node (ref "X6") (pin "2") (pinfunction "S_2") (pintype "passive"))
    )
    (net (code "58") (name "Net-(X6F-S)") (class "Default")
      (node (ref "R35") (pin "1") (pinfunction "1_1") (pintype "passive"))
      (node (ref "X6") (pin "6") (pinfunction "S_6") (pintype "passive"))
    )
    (net (code "59") (name "Net-(X7B-S)") (class "Default")
      (node (ref "R33") (pin "1") (pinfunction "1_1") (pintype "passive"))
      (node (ref "R34") (pin "2") (pinfunction "2_2") (pintype "passive"))
      (node (ref "X7") (pin "2") (pinfunction "S_2") (pintype "passive"))
    )
    (net (code "60") (name "Net-(X7C-S)") (class "Default")
      (node (ref "R30") (pin "1") (pinfunction "1_1") (pintype "passive"))
      (node (ref "X7") (pin "3") (pinfunction "S_3") (pintype "passive"))
    )
    (net (code "61") (name "Net-(X7D-S)") (class "Default")
      (node (ref "Q9") (pin "E") (pinfunction "E_E") (pintype "passive"))
      (node (ref "X7") (pin "4") (pinfunction "S_4") (pintype "passive"))
    )
    (net (code "62") (name "Net-(X7E-S)") (class "Default")
      (node (ref "Q10") (pin "E") (pinfunction "E_E") (pintype "passive"))
      (node (ref "X7") (pin "5") (pinfunction "S_5") (pintype "passive"))
    )
    (net (code "63") (name "Net-(X7F-S)") (class "Default")
      (node (ref "R31") (pin "1") (pinfunction "1_1") (pintype "passive"))
      (node (ref "X7") (pin "6") (pinfunction "S_6") (pintype "passive"))
    )
    (net (code "64") (name "Net-(X9B-1)") (class "Default")
      (node (ref "F4") (pin "2A") (pinfunction "2A_2A") (pintype "passive"))
      (node (ref "X9") (pin "2") (pinfunction "1_2") (pintype "passive"))
    )
    (net (code "65") (name "Net-(X10B-S)") (class "Default")
      (node (ref "C10") (pin "+") (pinfunction "+_+") (pintype "passive"))
      (node (ref "D4") (pin "A") (pinfunction "A_A") (pintype "passive"))
      (node (ref "D7") (pin "C") (pinfunction "C_C") (pintype "passive"))
      (node (ref "Q2") (pin "S") (pinfunction "S_S") (pintype "passive"))
      (node (ref "R12") (pin "2") (pinfunction "2_2") (pintype "passive"))
      (node (ref "R23") (pin "2") (pinfunction "2_2") (pintype "passive"))
      (node (ref "R26") (pin "1") (pinfunction "1_1") (pintype "passive"))
      (node (ref "R27") (pin "1") (pinfunction "1_1") (pintype "passive"))
      (node (ref "X10") (pin "2") (pinfunction "S_2") (pintype "passive"))
      (node (ref "X3") (pin "1") (pinfunction "S_1") (pintype "passive"))
    )
    (net (code "66") (name "Net-(X11A-S)") (class "Default")
      (node (ref "Q13") (pin "C") (pinfunction "C_C") (pintype "passive"))
      (node (ref "X11") (pin "1") (pinfunction "S_1") (pintype "passive"))
    )
    (net (code "67") (name "Net-(X12C-S)") (class "Default")
      (node (ref "R38") (pin "2") (pinfunction "2_2") (pintype "passive"))
      (node (ref "X12") (pin "3") (pinfunction "S_3") (pintype "passive"))
    )
    (net (code "68") (name "Net-(X12D-S)") (class "Default")
      (node (ref "R16") (pin "2") (pinfunction "2_2") (pintype "passive"))
      (node (ref "X12") (pin "4") (pinfunction "S_4") (pintype "passive"))
    )
    (net (code "69") (name "Net-(X12E-S)") (class "Default")
      (node (ref "R10") (pin "2") (pinfunction "2_2") (pintype "passive"))
      (node (ref "X12") (pin "5") (pinfunction "S_5") (pintype "passive"))
    )
    (net (code "70") (name "unconnected-(F2-Pad1B)") (class "Default")
      (node (ref "F2") (pin "1B") (pinfunction "1B_1B") (pintype "passive"))
    )
    (net (code "71") (name "unconnected-(F2-Pad2B)") (class "Default")
      (node (ref "F2") (pin "2B") (pinfunction "2B_2B") (pintype "passive"))
    )
    (net (code "72") (name "unconnected-(F3-Pad1B)") (class "Default")
      (node (ref "F3") (pin "1B") (pinfunction "1B_1B") (pintype "passive"))
    )
    (net (code "73") (name "unconnected-(F3-Pad2B)") (class "Default")
      (node (ref "F3") (pin "2B") (pinfunction "2B_2B") (pintype "passive"))
    )
    (net (code "74") (name "unconnected-(F4-Pad1B)") (class "Default")
      (node (ref "F4") (pin "1B") (pinfunction "1B_1B") (pintype "passive"))
    )
    (net (code "75") (name "unconnected-(F4-Pad2B)") (class "Default")
      (node (ref "F4") (pin "2B") (pinfunction "2B_2B") (pintype "passive"))
    )
    (net (code "76") (name "unconnected-(IC1-Pad2)") (class "Default")
      (node (ref "IC1") (pin "2") (pinfunction "2_2") (pintype "passive"))
    )
    (net (code "77") (name "unconnected-(IC1-Pad3)") (class "Default")
      (node (ref "IC1") (pin "3") (pinfunction "3_3") (pintype "passive"))
    )
    (net (code "78") (name "unconnected-(IC1-Pad5)") (class "Default")
      (node (ref "IC1") (pin "5") (pinfunction "5_5") (pintype "passive"))
    )
    (net (code "79") (name "unconnected-(IC1-Pad6)") (class "Default")
      (node (ref "IC1") (pin "6") (pinfunction "6_6") (pintype "passive"))
    )
    (net (code "80") (name "unconnected-(IC1-Pad21)") (class "Default")
      (node (ref "IC1") (pin "21") (pinfunction "21_21") (pintype "passive"))
    )
    (net (code "81") (name "unconnected-(IC1-Pad23)") (class "Default")
      (node (ref "IC1") (pin "23") (pinfunction "23_23") (pintype "passive"))
    )
    (net (code "82") (name "unconnected-(IC1-Pad24)") (class "Default")
      (node (ref "IC1") (pin "24") (pinfunction "24_24") (pintype "passive"))
    )
    (net (code "83") (name "unconnected-(IC1-Pad25)") (class "Default")
      (node (ref "IC1") (pin "25") (pinfunction "25_25") (pintype "passive"))
    )
    (net (code "84") (name "unconnected-(IC1-Pad26)") (class "Default")
      (node (ref "IC1") (pin "26") (pinfunction "26_26") (pintype "passive"))
    )
    (net (code "85") (name "unconnected-(IC1-Pad27)") (class "Default")
      (node (ref "IC1") (pin "27") (pinfunction "27_27") (pintype "passive"))
    )
    (net (code "86") (name "unconnected-(IC1-Pad28)") (class "Default")
      (node (ref "IC1") (pin "28") (pinfunction "28_28") (pintype "passive"))
    )
    (net (code "87") (name "unconnected-(K1B-OA-Pad12A)") (class "Default")
      (node (ref "K1") (pin "12A") (pinfunction "OA_12A") (pintype "passive"))
    )
    (net (code "88") (name "unconnected-(K1B-OB-Pad12B)") (class "Default")
      (node (ref "K1") (pin "12B") (pinfunction "OB_12B") (pintype "passive"))
    )
    (net (code "89") (name "unconnected-(OK1-BAS-Pad6)") (class "Default")
      (node (ref "OK1") (pin "6") (pinfunction "BAS_6") (pintype "passive"))
    )
  )
)
